# USB_to_UART.net
KiCad netlist of a schematic drawn in Altium Designer
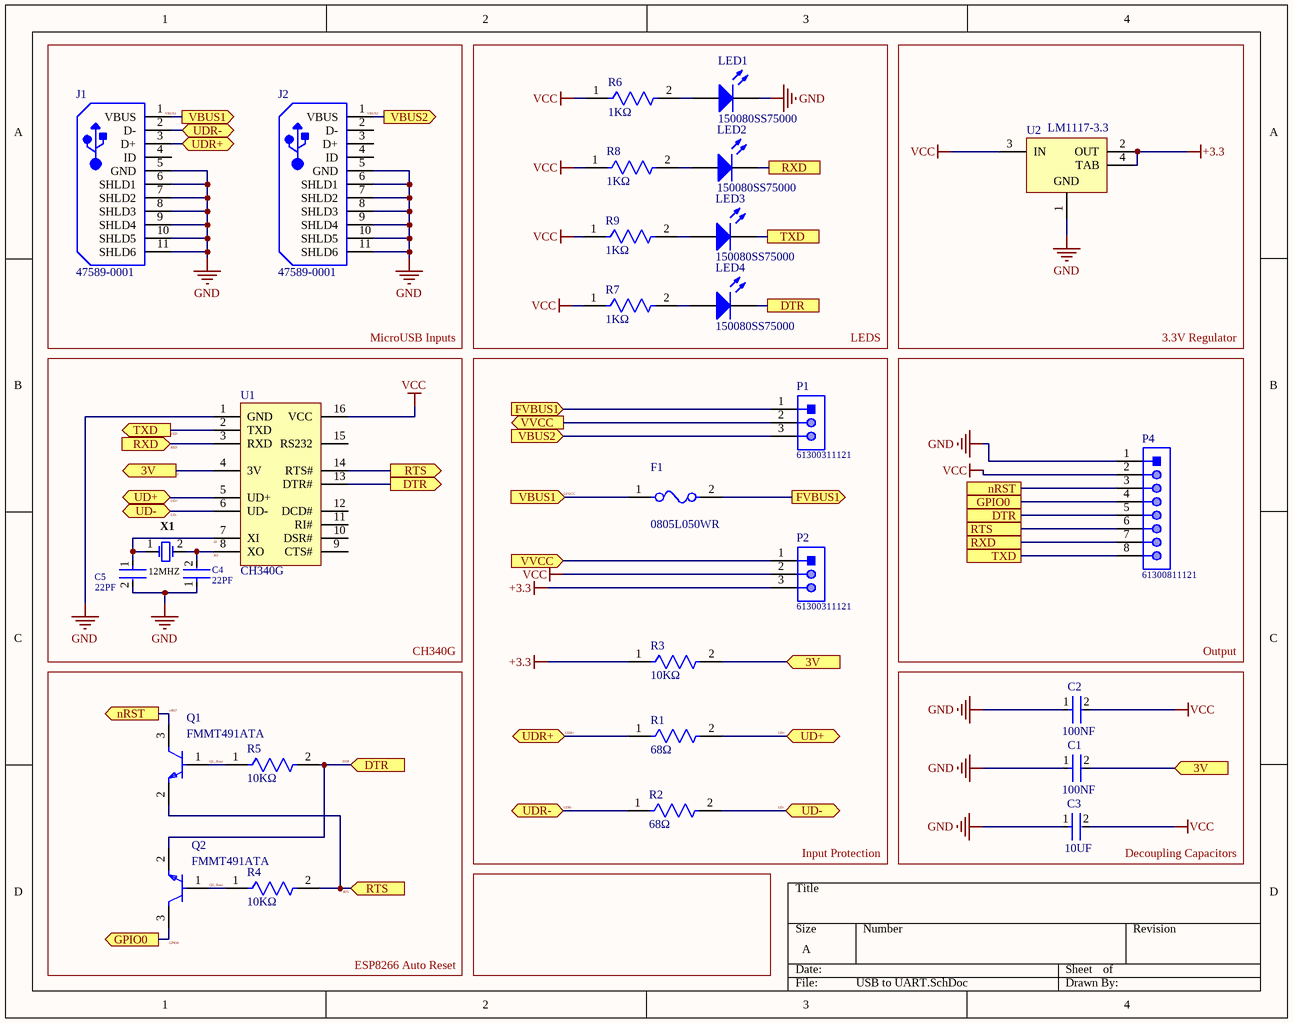
[diagram p0: USB to UART.SchDoc]

(export (version "E")
  (design (tool "Eeschema 10.0.6"))
  (components
    (comp (ref "C1")
      (value "100NF")
      (footprint "FP-C0805C-DN-MFG")
      (description "Capacitor; Ceramic; Cap; 22.0pF; Tol 5%; SMT; Vol-Rtg 50V; C0G; Tape and Reel")
      (fields
        (field (name "OCTOPART") "https://octopart.com/c0805c220j5gactu-kemet-145470")
        (field (name "MANUFACTURER") "KEMET")
      )
      (libsource (lib "Altium Content Vault") (part "b4654b650e69147ec39a6b967a45e02"))
    )
    (comp (ref "C2")
      (value "100NF")
      (footprint "FP-C0805C-DN-MFG")
      (description "Capacitor; Ceramic; Cap; 22.0pF; Tol 5%; SMT; Vol-Rtg 50V; C0G; Tape and Reel")
      (fields
        (field (name "OCTOPART") "https://octopart.com/c0805c220j5gactu-kemet-145470")
        (field (name "MANUFACTURER") "KEMET")
      )
      (libsource (lib "Altium Content Vault") (part "b4654b650e69147ec39a6b967a45e02"))
    )
    (comp (ref "C3")
      (value "10UF")
      (footprint "FP-C0805C-DN-MFG")
      (description "Capacitor; Ceramic; Cap; 22.0pF; Tol 5%; SMT; Vol-Rtg 50V; C0G; Tape and Reel")
      (fields
        (field (name "OCTOPART") "https://octopart.com/c0805c220j5gactu-kemet-145470")
        (field (name "MANUFACTURER") "KEMET")
      )
      (libsource (lib "Altium Content Vault") (part "b4654b650e69147ec39a6b967a45e02"))
    )
    (comp (ref "C4")
      (value "22PF")
      (footprint "FP-C0805C-DN-MFG")
      (description "Capacitor; Ceramic; Cap; 22.0pF; Tol 5%; SMT; Vol-Rtg 50V; C0G; Tape and Reel")
      (fields
        (field (name "OCTOPART") "https://octopart.com/c0805c220j5gactu-kemet-145470")
        (field (name "MANUFACTURER") "KEMET")
      )
      (libsource (lib "Altium Content Vault") (part "b4654b650e69147ec39a6b967a45e02"))
    )
    (comp (ref "C5")
      (value "22PF")
      (footprint "FP-C0805C-DN-MFG")
      (description "Capacitor; Ceramic; Cap; 22.0pF; Tol 5%; SMT; Vol-Rtg 50V; C0G; Tape and Reel")
      (fields
        (field (name "OCTOPART") "https://octopart.com/c0805c220j5gactu-kemet-145470")
        (field (name "MANUFACTURER") "KEMET")
      )
      (libsource (lib "Altium Content Vault") (part "b4654b650e69147ec39a6b967a45e02"))
    )
    (comp (ref "F1")
      (value "0805L050WR")
      (footprint "FP-0805L-MFG")
      (description "PTC RESET FUSE 6V 500MA 0805")
      (fields
        (field (name "MANUFACTURER") "Littelfuse Inc.")
        (field (name "OCTOPART") "https://octopart.com/0805l050wr-littelfuse-673858")
      )
      (libsource (lib "Altium Content Vault") (part "5bcf9b9f640e542cf0359d10258e979"))
    )
    (comp (ref "J1")
      (value "47589-0001")
      (footprint "MOLX-47589-0001_V")
      (description "Right Angle Female Type AB Micro USB Connector, 30 V, 1.8 A, -30 to 85 degC, RoHS, Tape and Reel")
      (fields (field (name "MANUFACTURER") "Molex"))
      (libsource (lib "Altium Content Vault") (part "USB-5-6SHLD"))
    )
    (comp (ref "J2")
      (value "47589-0001")
      (footprint "MOLX-47589-0001_V")
      (description "Right Angle Female Type AB Micro USB Connector, 30 V, 1.8 A, -30 to 85 degC, RoHS, Tape and Reel")
      (fields (field (name "MANUFACTURER") "Molex"))
      (libsource (lib "Altium Content Vault") (part "USB-5-6SHLD"))
    )
    (comp (ref "LED1")
      (value "150080SS75000")
      (footprint "0805_A")
      (description "SMD mono-color Chip LED, WL-SMCW, Super Red")
      (fields (field (name "MANUFACTURER") "Wuerth Elektronik"))
      (libsource (lib "Altium Content Vault") (part "WE-LED_K1A2-2"))
    )
    (comp (ref "LED2")
      (value "150080SS75000")
      (footprint "0805_A")
      (description "SMD mono-color Chip LED, WL-SMCW, Super Red")
      (fields (field (name "MANUFACTURER") "Wuerth Elektronik"))
      (libsource (lib "Altium Content Vault") (part "WE-LED_K1A2-2"))
    )
    (comp (ref "LED3")
      (value "150080SS75000")
      (footprint "0805_A")
      (description "SMD mono-color Chip LED, WL-SMCW, Super Red")
      (fields (field (name "MANUFACTURER") "Wuerth Elektronik"))
      (libsource (lib "Altium Content Vault") (part "WE-LED_K1A2-2"))
    )
    (comp (ref "LED4")
      (value "150080SS75000")
      (footprint "0805_A")
      (description "SMD mono-color Chip LED, WL-SMCW, Super Red")
      (fields (field (name "MANUFACTURER") "Wuerth Elektronik"))
      (libsource (lib "Altium Content Vault") (part "WE-LED_K1A2-2"))
    )
    (comp (ref "P1")
      (value "61300311121")
      (footprint "61300311121")
      (description "THT Vertical Pin Header WR-PHD, Pitch 2.54 mm, Single Row, 3 pins")
      (fields (field (name "MANUFACTURER") "Wurth Elektronik") (field (name "PUBLISHER") "WurthElektronik"))
      (libsource (lib "Altium Content Vault") (part "WE-CN-1P-M-R3"))
    )
    (comp (ref "P2")
      (value "61300311121")
      (footprint "61300311121")
      (description "THT Vertical Pin Header WR-PHD, Pitch 2.54 mm, Single Row, 3 pins")
      (fields (field (name "MANUFACTURER") "Wurth Elektronik") (field (name "PUBLISHER") "WurthElektronik"))
      (libsource (lib "Altium Content Vault") (part "WE-CN-1P-M-R3"))
    )
    (comp (ref "P4")
      (value "61300811121")
      (footprint "61300811121")
      (description "THT Vertical Pin Header WR-PHD, Pitch 2.54 mm, Single Row, 8 pins")
      (fields (field (name "MANUFACTURER") "Wurth Elektronik") (field (name "PUBLISHER") "WurthElektronik"))
      (libsource (lib "Altium Content Vault") (part "WE-CN-1P-M-R8"))
    )
    (comp (ref "Q1")
      (value "FMMT491ATA")
      (footprint "FP-SOT23_Type_DN-MFG")
      (description "TRANSISTOR NPN 40V 1A SOT23-3 - ANY NPN TRANSOSTOR LIKE S8050 2N2222...")
      (fields
        (field (name "OCTOPART") "https://octopart.com/fmmt491ata-diodes+inc.-356338")
        (field (name "MANUFACTURER") "Diodes")
      )
      (libsource (lib "Altium Content Vault") (part "b44e953556f554d0102664c7d152cb4"))
    )
    (comp (ref "Q2")
      (value "FMMT491ATA")
      (footprint "FP-SOT23_Type_DN-MFG")
      (description "TRANSISTOR NPN 40V 1A SOT23-3 - ANY NPN TRANSOSTOR LIKE S8050 2N2222...")
      (fields
        (field (name "OCTOPART") "https://octopart.com/fmmt491ata-diodes+inc.-356338")
        (field (name "MANUFACTURER") "Diodes")
      )
      (libsource (lib "Altium Content Vault") (part "b44e953556f554d0102664c7d152cb4"))
    )
    (comp (ref "R1")
      (value "68Ω")
      (footprint "FP-CRCW0805-e3-IPC_C")
      (description "RES Thick Film, 68Ω, 1%, 0.125W, 100ppm/°C, 0805")
      (fields (field (name "TOLERANCE") "1%"))
      (libsource (lib "Altium Content Vault") (part "1029c3af85768c4190bb7ad29bc67b5"))
    )
    (comp (ref "R2")
      (value "68Ω")
      (footprint "FP-CRCW0805-e3-IPC_C")
      (description "RES Thick Film, 68Ω, 1%, 0.125W, 100ppm/°C, 0805")
      (fields (field (name "TOLERANCE") "1%"))
      (libsource (lib "Altium Content Vault") (part "1029c3af85768c4190bb7ad29bc67b5"))
    )
    (comp (ref "R3")
      (value "10KΩ")
      (footprint "FP-CRCW0805-e3-IPC_C")
      (description "RES Thick Film, 10KΩ, 1%, 0.125W, 100ppm/°C, 0805")
      (fields (field (name "TOLERANCE") "1%"))
      (libsource (lib "Altium Content Vault") (part "1029c3af85768c4190bb7ad29bc67b5"))
    )
    (comp (ref "R4")
      (value "10KΩ")
      (footprint "FP-CRCW0805-e3-IPC_C")
      (description "RES Thick Film, 10kΩ, 1%, 0.125W, 100ppm/°C, 0805")
      (fields (field (name "TOLERANCE") "1%"))
      (libsource (lib "Altium Content Vault") (part "1029c3af85768c4190bb7ad29bc67b5"))
    )
    (comp (ref "R5")
      (value "10KΩ")
      (footprint "FP-CRCW0805-e3-IPC_C")
      (description "RES Thick Film, 10kΩ, 1%, 0.125W, 100ppm/°C, 0805")
      (fields (field (name "TOLERANCE") "1%"))
      (libsource (lib "Altium Content Vault") (part "1029c3af85768c4190bb7ad29bc67b5"))
    )
    (comp (ref "R6")
      (value "1KΩ")
      (footprint "FP-CRCW0805-e3-IPC_C")
      (description "RES Thick Film, 1kΩ, 1%, 0.125W, 100ppm/°C, 0805")
      (fields (field (name "TOLERANCE") "1%"))
      (libsource (lib "Altium Content Vault") (part "1029c3af85768c4190bb7ad29bc67b5"))
    )
    (comp (ref "R7")
      (value "1KΩ")
      (footprint "FP-CRCW0805-e3-IPC_C")
      (description "RES Thick Film, 1KΩ, 1%, 0.125W, 100ppm/°C, 0805")
      (fields (field (name "TOLERANCE") "1%"))
      (libsource (lib "Altium Content Vault") (part "1029c3af85768c4190bb7ad29bc67b5"))
    )
    (comp (ref "R8")
      (value "1KΩ")
      (footprint "FP-CRCW0805-e3-IPC_C")
      (description "RES Thick Film, 1KΩ, 1%, 0.125W, 100ppm/°C, 0805")
      (fields (field (name "TOLERANCE") "1%"))
      (libsource (lib "Altium Content Vault") (part "1029c3af85768c4190bb7ad29bc67b5"))
    )
    (comp (ref "R9")
      (value "1KΩ")
      (footprint "FP-CRCW0805-e3-IPC_C")
      (description "RES Thick Film, 1KΩ, 1%, 0.125W, 100ppm/°C, 0805")
      (fields (field (name "TOLERANCE") "1%"))
      (libsource (lib "Altium Content Vault") (part "1029c3af85768c4190bb7ad29bc67b5"))
    )
    (comp (ref "U1")
      (value "CH340G")
      (footprint "D0016A_L")
      (description "High Speed CMOS 8-Channel Analog Multiplexer/Demultiplexer, D0016A, TUBE")
      (fields
        (field (name "MANUFACTURER") "Texas Instruments")
        (field (name "GENERIC PART NUMBER") "CD74HC4051")
      )
      (libsource (lib "Altium Content Vault") (part "TI-CD74HCX4051-16"))
    )
    (comp (ref "U2")
      (value "LM1117-3.3")
      (footprint "DCY0004A_L")
      (description "800mA Low-Dropout Linear Regulator, 4-pin SOT-223, Pb-Free")
      (fields
        (field (name "PARTNUMBER") "LM1117MP-3.3/NOPB")
        (field (name "MANUFACTURER") "Texas Instruments")
      )
      (libsource (lib "Altium Content Vault") (part "PM-REG-LM1086-SOT4"))
    )
    (comp (ref "X1")
      (value "12MHZ")
      (footprint "FOX-FOXSLF-2_V")
      (description "Resistance Weld Thru-Hole Crystal, 12 MHz, +/-30 ppm, -20 to 70 degC, 2-Pin THD, RoHS, Bulk")
      (libsource (lib "Altium Content Vault") (part "XTAL-1-2-2"))
    )
  )
  (nets
    (net (code "1") (name "+3.3") (class "Default")
      (node (ref "P2") (pin "3") (pinfunction "3_3") (pintype "passive"))
      (node (ref "R3") (pin "1") (pinfunction "1_1") (pintype "passive"))
      (node (ref "U2") (pin "2") (pinfunction "OUT_2") (pintype "power_in"))
      (node (ref "U2") (pin "4") (pinfunction "TAB_4") (pintype "power_in"))
    )
    (net (code "2") (name "/3V") (class "Default")
      (node (ref "C1") (pin "2") (pinfunction "2_2") (pintype "passive"))
      (node (ref "R3") (pin "2") (pinfunction "2_2") (pintype "passive"))
      (node (ref "U1") (pin "4") (pinfunction "3V_4") (pintype "passive"))
    )
    (net (code "3") (name "/DTR") (class "Default")
      (node (ref "LED4") (pin "1") (pinfunction "K_1") (pintype "passive"))
      (node (ref "P4") (pin "5") (pinfunction "5_5") (pintype "passive"))
      (node (ref "Q2") (pin "2") (pinfunction "E_2") (pintype "passive"))
      (node (ref "R5") (pin "2") (pinfunction "2_2") (pintype "passive"))
      (node (ref "U1") (pin "13") (pinfunction "DTR#_13") (pintype "passive"))
    )
    (net (code "4") (name "/FVBUS1") (class "Default")
      (node (ref "F1") (pin "2") (pinfunction "2_2") (pintype "passive"))
      (node (ref "P1") (pin "1") (pinfunction "1_1") (pintype "passive"))
    )
    (net (code "5") (name "/GPIO0") (class "Default")
      (node (ref "P4") (pin "4") (pinfunction "4_4") (pintype "passive"))
      (node (ref "Q2") (pin "3") (pinfunction "C_3") (pintype "passive"))
    )
    (net (code "6") (name "/Q1_Base") (class "Default")
      (node (ref "Q1") (pin "1") (pinfunction "B_1") (pintype "passive"))
      (node (ref "R5") (pin "1") (pinfunction "1_1") (pintype "passive"))
    )
    (net (code "7") (name "/Q2_Base") (class "Default")
      (node (ref "Q2") (pin "1") (pinfunction "B_1") (pintype "passive"))
      (node (ref "R4") (pin "1") (pinfunction "1_1") (pintype "passive"))
    )
    (net (code "8") (name "/RTS") (class "Default")
      (node (ref "P4") (pin "6") (pinfunction "6_6") (pintype "passive"))
      (node (ref "Q1") (pin "2") (pinfunction "E_2") (pintype "passive"))
      (node (ref "R4") (pin "2") (pinfunction "2_2") (pintype "passive"))
      (node (ref "U1") (pin "14") (pinfunction "RTS#_14") (pintype "passive"))
    )
    (net (code "9") (name "/RXD") (class "Default")
      (node (ref "LED2") (pin "1") (pinfunction "K_1") (pintype "passive"))
      (node (ref "P4") (pin "7") (pinfunction "7_7") (pintype "passive"))
      (node (ref "U1") (pin "3") (pinfunction "RXD_3") (pintype "passive"))
    )
    (net (code "10") (name "/TXD") (class "Default")
      (node (ref "LED3") (pin "1") (pinfunction "K_1") (pintype "passive"))
      (node (ref "P4") (pin "8") (pinfunction "8_8") (pintype "passive"))
      (node (ref "U1") (pin "2") (pinfunction "TXD_2") (pintype "passive"))
    )
    (net (code "11") (name "/UD+") (class "Default")
      (node (ref "R1") (pin "2") (pinfunction "2_2") (pintype "passive"))
      (node (ref "U1") (pin "5") (pinfunction "UD+_5") (pintype "passive"))
    )
    (net (code "12") (name "/UD-") (class "Default")
      (node (ref "R2") (pin "2") (pinfunction "2_2") (pintype "passive"))
      (node (ref "U1") (pin "6") (pinfunction "UD-_6") (pintype "passive"))
    )
    (net (code "13") (name "/UDR+") (class "Default")
      (node (ref "J1") (pin "3") (pinfunction "D+_3") (pintype "passive"))
      (node (ref "R1") (pin "1") (pinfunction "1_1") (pintype "passive"))
    )
    (net (code "14") (name "/UDR-") (class "Default")
      (node (ref "J1") (pin "2") (pinfunction "D-_2") (pintype "passive"))
      (node (ref "R2") (pin "1") (pinfunction "1_1") (pintype "passive"))
    )
    (net (code "16") (name "/VBUS1") (class "Default")
      (node (ref "F1") (pin "1") (pinfunction "1_1") (pintype "passive"))
      (node (ref "J1") (pin "1") (pinfunction "VBUS_1") (pintype "passive"))
    )
    (net (code "17") (name "/VBUS2") (class "Default")
      (node (ref "J2") (pin "1") (pinfunction "VBUS_1") (pintype "passive"))
      (node (ref "P1") (pin "3") (pinfunction "3_3") (pintype "passive"))
    )
    (net (code "18") (name "/VVCC") (class "Default")
      (node (ref "P1") (pin "2") (pinfunction "2_2") (pintype "passive"))
      (node (ref "P2") (pin "1") (pinfunction "1_1") (pintype "passive"))
    )
    (net (code "19") (name "/XI") (class "Default")
      (node (ref "C5") (pin "1") (pinfunction "1_1") (pintype "passive"))
      (node (ref "U1") (pin "7") (pinfunction "XI_7") (pintype "power_in"))
      (node (ref "X1") (pin "1") (pinfunction "1_1") (pintype "passive"))
    )
    (net (code "20") (name "/XO") (class "Default")
      (node (ref "C4") (pin "2") (pinfunction "2_2") (pintype "passive"))
      (node (ref "U1") (pin "8") (pinfunction "XO_8") (pintype "power_in"))
      (node (ref "X1") (pin "2") (pinfunction "2_2") (pintype "passive"))
    )
    (net (code "21") (name "/nRST") (class "Default")
      (node (ref "P4") (pin "3") (pinfunction "3_3") (pintype "passive"))
      (node (ref "Q1") (pin "3") (pinfunction "C_3") (pintype "passive"))
    )
    (net (code "22") (name "GND") (class "Default")
      (node (ref "C1") (pin "1") (pinfunction "1_1") (pintype "passive"))
      (node (ref "C2") (pin "1") (pinfunction "1_1") (pintype "passive"))
      (node (ref "C3") (pin "1") (pinfunction "1_1") (pintype "passive"))
      (node (ref "C4") (pin "1") (pinfunction "1_1") (pintype "passive"))
      (node (ref "C5") (pin "2") (pinfunction "2_2") (pintype "passive"))
      (node (ref "J1") (pin "10") (pinfunction "SHLD5_10") (pintype "passive"))
      (node (ref "J1") (pin "11") (pinfunction "SHLD6_11") (pintype "passive"))
      (node (ref "J1") (pin "5") (pinfunction "GND_5") (pintype "passive"))
      (node (ref "J1") (pin "6") (pinfunction "SHLD1_6") (pintype "passive"))
      (node (ref "J1") (pin "7") (pinfunction "SHLD2_7") (pintype "passive"))
      (node (ref "J1") (pin "8") (pinfunction "SHLD3_8") (pintype "passive"))
      (node (ref "J1") (pin "9") (pinfunction "SHLD4_9") (pintype "passive"))
      (node (ref "J2") (pin "10") (pinfunction "SHLD5_10") (pintype "passive"))
      (node (ref "J2") (pin "11") (pinfunction "SHLD6_11") (pintype "passive"))
      (node (ref "J2") (pin "5") (pinfunction "GND_5") (pintype "passive"))
      (node (ref "J2") (pin "6") (pinfunction "SHLD1_6") (pintype "passive"))
      (node (ref "J2") (pin "7") (pinfunction "SHLD2_7") (pintype "passive"))
      (node (ref "J2") (pin "8") (pinfunction "SHLD3_8") (pintype "passive"))
      (node (ref "J2") (pin "9") (pinfunction "SHLD4_9") (pintype "passive"))
      (node (ref "LED1") (pin "1") (pinfunction "K_1") (pintype "passive"))
      (node (ref "P4") (pin "1") (pinfunction "1_1") (pintype "passive"))
      (node (ref "U1") (pin "1") (pinfunction "GND_1") (pintype "passive"))
      (node (ref "U2") (pin "1") (pinfunction "GND_1") (pintype "power_in"))
    )
    (net (code "23") (name "Net-(LED1-A)") (class "Default")
      (node (ref "LED1") (pin "2") (pinfunction "A_2") (pintype "passive"))
      (node (ref "R6") (pin "2") (pinfunction "2_2") (pintype "passive"))
    )
    (net (code "24") (name "Net-(LED2-A)") (class "Default")
      (node (ref "LED2") (pin "2") (pinfunction "A_2") (pintype "passive"))
      (node (ref "R8") (pin "2") (pinfunction "2_2") (pintype "passive"))
    )
    (net (code "25") (name "Net-(LED3-A)") (class "Default")
      (node (ref "LED3") (pin "2") (pinfunction "A_2") (pintype "passive"))
      (node (ref "R9") (pin "2") (pinfunction "2_2") (pintype "passive"))
    )
    (net (code "26") (name "Net-(LED4-A)") (class "Default")
      (node (ref "LED4") (pin "2") (pinfunction "A_2") (pintype "passive"))
      (node (ref "R7") (pin "2") (pinfunction "2_2") (pintype "passive"))
    )
    (net (code "27") (name "VCC") (class "Default")
      (node (ref "C2") (pin "2") (pinfunction "2_2") (pintype "passive"))
      (node (ref "C3") (pin "2") (pinfunction "2_2") (pintype "passive"))
      (node (ref "P2") (pin "2") (pinfunction "2_2") (pintype "passive"))
      (node (ref "P4") (pin "2") (pinfunction "2_2") (pintype "passive"))
      (node (ref "R6") (pin "1") (pinfunction "1_1") (pintype "passive"))
      (node (ref "R7") (pin "1") (pinfunction "1_1") (pintype "passive"))
      (node (ref "R8") (pin "1") (pinfunction "1_1") (pintype "passive"))
      (node (ref "R9") (pin "1") (pinfunction "1_1") (pintype "passive"))
      (node (ref "U1") (pin "16") (pinfunction "VCC_16") (pintype "power_in"))
      (node (ref "U2") (pin "3") (pinfunction "IN_3") (pintype "power_in"))
    )
    (net (code "28") (name "unconnected-(J1-ID-Pad4)") (class "Default")
      (node (ref "J1") (pin "4") (pinfunction "ID_4") (pintype "passive"))
    )
    (net (code "29") (name "unconnected-(J2-D+-Pad3)") (class "Default")
      (node (ref "J2") (pin "3") (pinfunction "D+_3") (pintype "passive"))
    )
    (net (code "30") (name "unconnected-(J2-D--Pad2)") (class "Default")
      (node (ref "J2") (pin "2") (pinfunction "D-_2") (pintype "passive"))
    )
    (net (code "31") (name "unconnected-(J2-ID-Pad4)") (class "Default")
      (node (ref "J2") (pin "4") (pinfunction "ID_4") (pintype "passive"))
    )
    (net (code "32") (name "unconnected-(U1-CTS#-Pad9)") (class "Default")
      (node (ref "U1") (pin "9") (pinfunction "CTS#_9") (pintype "passive"))
    )
    (net (code "33") (name "unconnected-(U1-DCD#-Pad12)") (class "Default")
      (node (ref "U1") (pin "12") (pinfunction "DCD#_12") (pintype "passive"))
    )
    (net (code "34") (name "unconnected-(U1-DSR#-Pad10)") (class "Default")
      (node (ref "U1") (pin "10") (pinfunction "DSR#_10") (pintype "passive"))
    )
    (net (code "35") (name "unconnected-(U1-RI#-Pad11)") (class "Default")
      (node (ref "U1") (pin "11") (pinfunction "RI#_11") (pintype "passive"))
    )
    (net (code "36") (name "unconnected-(U1-RS232-Pad15)") (class "Default")
      (node (ref "U1") (pin "15") (pinfunction "RS232_15") (pintype "passive"))
    )
  )
)
